# nixie_peripherals.net
KiCad netlist of a schematic drawn in Altium Designer
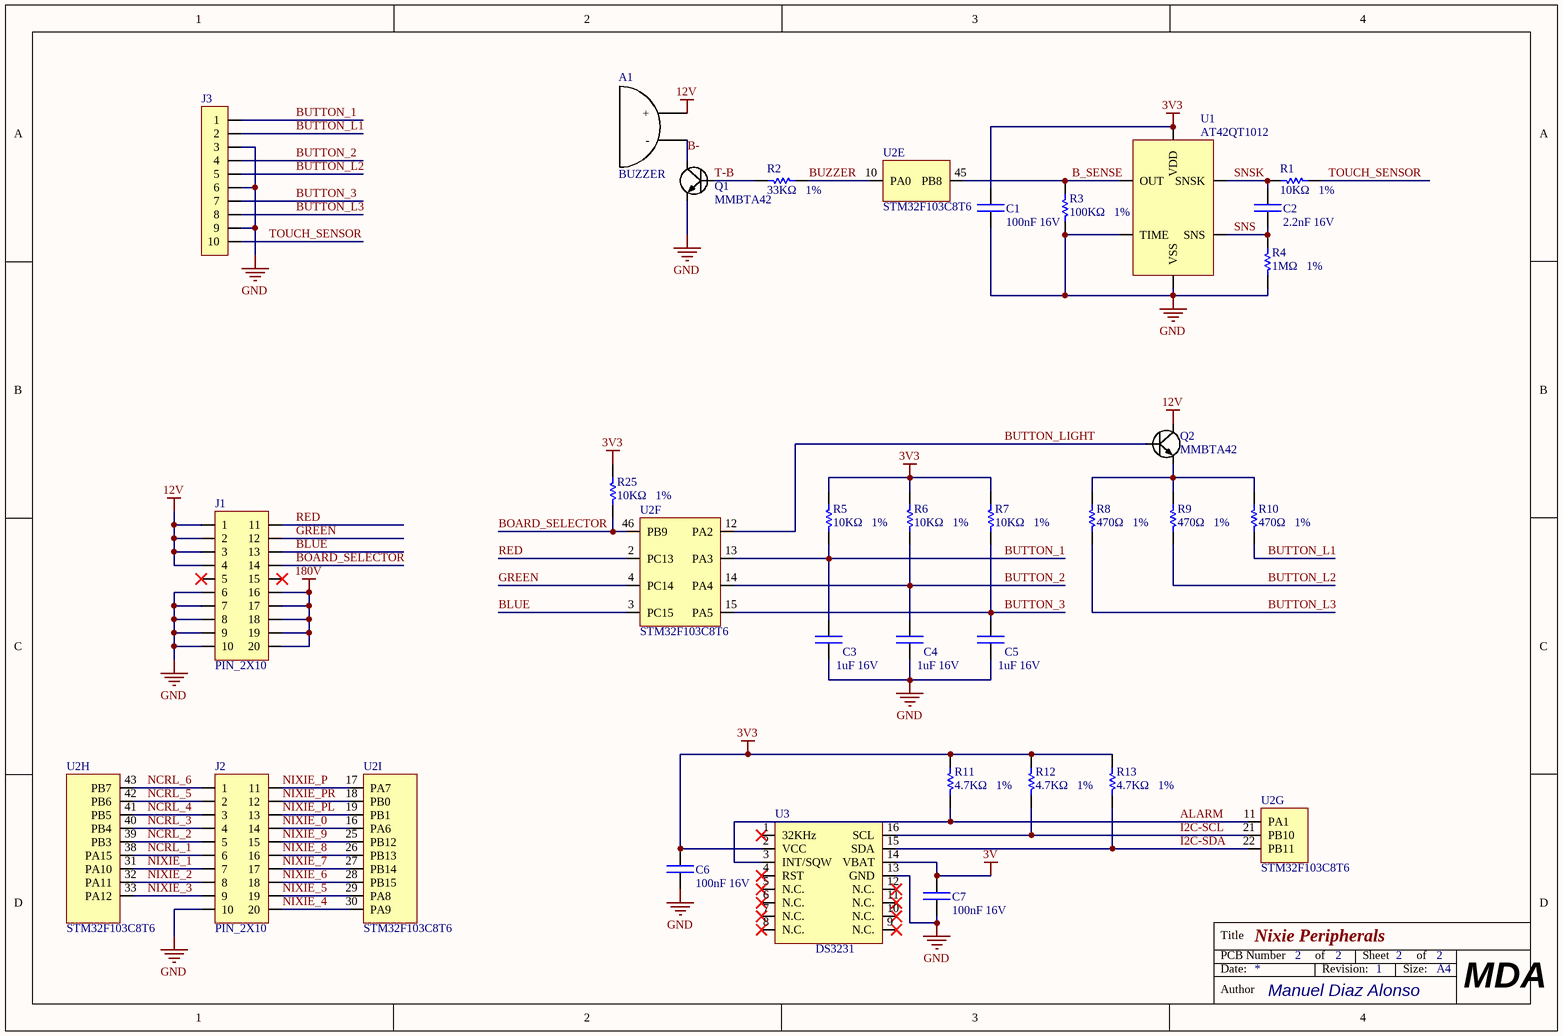
[diagram p0: nixie_peripherals.SchDoc]

(export (version "E")
  (design (tool "Eeschema 10.0.6"))
  (components
    (comp (ref "A1") (value "BUZZER") (footprint "BUZZER") (libsource (lib "Nixielib") (part "BUZZER")))
    (comp (ref "C1") (value "100nF 16V") (footprint "0603") (libsource (lib "Nixielib") (part "CAP")))
    (comp (ref "C2") (value "2.2nF 16V") (footprint "0603") (libsource (lib "Nixielib") (part "CAP")))
    (comp (ref "C3") (value "1uF 16V") (footprint "0603") (libsource (lib "Nixielib") (part "CAP")))
    (comp (ref "C4") (value "1uF 16V") (footprint "0603") (libsource (lib "Nixielib") (part "CAP")))
    (comp (ref "C5") (value "1uF 16V") (footprint "0603") (libsource (lib "Nixielib") (part "CAP")))
    (comp (ref "C6") (value "100nF 16V") (footprint "0603") (libsource (lib "Nixielib") (part "CAP")))
    (comp (ref "C7") (value "100nF 16V") (footprint "0603") (libsource (lib "Nixielib") (part "CAP")))
    (comp (ref "J1")
      (value "PIN_2X10")
      (footprint "PIN_2X10_SKT")
      (description "SSW-110-01-L-D")
      (libsource (lib "MyLib") (part "PIN_2X10"))
    )
    (comp (ref "J2")
      (value "PIN_2X10")
      (footprint "PIN_2X10_SKT")
      (description "SSW-110-01-L-D")
      (libsource (lib "MyLib") (part "PIN_2X10"))
    )
    (comp (ref "J3")
      (value "HEADERx10")
      (footprint "HEADERx10")
      (description "1-282837-0")
      (libsource (lib "Nixielib") (part "HEADERx10"))
    )
    (comp (ref "Q1") (value "MMBTA42") (footprint "SOT-23") (libsource (lib "Nixielib") (part "NPN")))
    (comp (ref "Q2") (value "MMBTA42") (footprint "SOT-23") (libsource (lib "Nixielib") (part "NPN")))
    (comp (ref "R1") (value "10KΩ   1%") (footprint "0603") (libsource (lib "Nixielib") (part "RES")))
    (comp (ref "R2") (value "33KΩ   1%") (footprint "0603") (libsource (lib "Nixielib") (part "RES")))
    (comp (ref "R3") (value "100KΩ   1%") (footprint "0603") (libsource (lib "Nixielib") (part "RES")))
    (comp (ref "R4") (value "1MΩ   1%") (footprint "0603") (libsource (lib "Nixielib") (part "RES")))
    (comp (ref "R5") (value "10KΩ   1%") (footprint "0603") (libsource (lib "Nixielib") (part "RES")))
    (comp (ref "R6") (value "10KΩ   1%") (footprint "0603") (libsource (lib "Nixielib") (part "RES")))
    (comp (ref "R7") (value "10KΩ   1%") (footprint "0603") (libsource (lib "Nixielib") (part "RES")))
    (comp (ref "R8") (value "470Ω   1%") (footprint "0603") (libsource (lib "Nixielib") (part "RES")))
    (comp (ref "R9") (value "470Ω   1%") (footprint "0603") (libsource (lib "Nixielib") (part "RES")))
    (comp (ref "R10") (value "470Ω   1%") (footprint "0603") (libsource (lib "Nixielib") (part "RES")))
    (comp (ref "R11") (value "4.7KΩ   1%") (footprint "0603") (libsource (lib "Nixielib") (part "RES")))
    (comp (ref "R12") (value "4.7KΩ   1%") (footprint "0603") (libsource (lib "Nixielib") (part "RES")))
    (comp (ref "R13") (value "4.7KΩ   1%") (footprint "0603") (libsource (lib "Nixielib") (part "RES")))
    (comp (ref "R25") (value "10KΩ   1%") (footprint "0603") (libsource (lib "Nixielib") (part "RES")))
    (comp (ref "U1")
      (value "AT42QT1012")
      (footprint "SOT-23-6")
      (libsource (lib "Nixielib") (part "AT42QT1012"))
    )
    (comp (ref "U2")
      (value "STM32F103C8T6")
      (footprint "LQFP48")
      (libsource (lib "MyLib") (part "STM32F103C8T6"))
    )
    (comp (ref "U3") (value "DS3231") (footprint "SO16W") (libsource (lib "Nixielib") (part "DS3231")))
  )
  (nets
    (net (code "1") (name "/ALARM") (class "Default")
      (node (ref "R11") (pin "1") (pinfunction "1_1") (pintype "passive"))
      (node (ref "U2") (pin "11") (pinfunction "PA1_11") (pintype "passive"))
      (node (ref "U3") (pin "3") (pinfunction "INT/SQW_3") (pintype "passive"))
    )
    (net (code "2") (name "/B-") (class "Default")
      (node (ref "A1") (pin "2") (pinfunction "-_2") (pintype "passive"))
      (node (ref "Q1") (pin "3") (pinfunction "C_3") (pintype "passive"))
    )
    (net (code "3") (name "/BLUE") (class "Default")
      (node (ref "J1") (pin "13") (pinfunction "13_13") (pintype "passive"))
      (node (ref "U2") (pin "3") (pinfunction "PC15_3") (pintype "passive"))
    )
    (net (code "4") (name "/BOARD_SELECTOR") (class "Default")
      (node (ref "J1") (pin "14") (pinfunction "14_14") (pintype "passive"))
      (node (ref "R25") (pin "2") (pinfunction "2_2") (pintype "passive"))
      (node (ref "U2") (pin "46") (pinfunction "PB9_46") (pintype "passive"))
    )
    (net (code "5") (name "/BUTTON_1") (class "Default")
      (node (ref "C3") (pin "2") (pinfunction "2_2") (pintype "passive"))
      (node (ref "J3") (pin "1") (pinfunction "1_1") (pintype "passive"))
      (node (ref "R5") (pin "1") (pinfunction "1_1") (pintype "passive"))
      (node (ref "U2") (pin "13") (pinfunction "PA3_13") (pintype "passive"))
    )
    (net (code "6") (name "/BUTTON_2") (class "Default")
      (node (ref "C4") (pin "2") (pinfunction "2_2") (pintype "passive"))
      (node (ref "J3") (pin "4") (pinfunction "4_4") (pintype "passive"))
      (node (ref "R6") (pin "1") (pinfunction "1_1") (pintype "passive"))
      (node (ref "U2") (pin "14") (pinfunction "PA4_14") (pintype "passive"))
    )
    (net (code "7") (name "/BUTTON_3") (class "Default")
      (node (ref "C5") (pin "2") (pinfunction "2_2") (pintype "passive"))
      (node (ref "J3") (pin "7") (pinfunction "7_7") (pintype "passive"))
      (node (ref "R7") (pin "1") (pinfunction "1_1") (pintype "passive"))
      (node (ref "U2") (pin "15") (pinfunction "PA5_15") (pintype "passive"))
    )
    (net (code "8") (name "/BUTTON_L1") (class "Default")
      (node (ref "J3") (pin "2") (pinfunction "2_2") (pintype "passive"))
      (node (ref "R10") (pin "2") (pinfunction "2_2") (pintype "passive"))
    )
    (net (code "9") (name "/BUTTON_L2") (class "Default")
      (node (ref "J3") (pin "5") (pinfunction "5_5") (pintype "passive"))
      (node (ref "R9") (pin "2") (pinfunction "2_2") (pintype "passive"))
    )
    (net (code "10") (name "/BUTTON_L3") (class "Default")
      (node (ref "J3") (pin "8") (pinfunction "8_8") (pintype "passive"))
      (node (ref "R8") (pin "2") (pinfunction "2_2") (pintype "passive"))
    )
    (net (code "11") (name "/BUTTON_LIGHT") (class "Default")
      (node (ref "Q2") (pin "1") (pinfunction "B_1") (pintype "passive"))
      (node (ref "U2") (pin "12") (pinfunction "PA2_12") (pintype "passive"))
    )
    (net (code "12") (name "/BUZZER") (class "Default")
      (node (ref "R2") (pin "2") (pinfunction "2_2") (pintype "passive"))
      (node (ref "U2") (pin "10") (pinfunction "PA0_10") (pintype "passive"))
    )
    (net (code "13") (name "/B_SENSE") (class "Default")
      (node (ref "R3") (pin "2") (pinfunction "2_2") (pintype "passive"))
      (node (ref "U1") (pin "1") (pinfunction "OUT_1") (pintype "passive"))
      (node (ref "U2") (pin "45") (pinfunction "PB8_45") (pintype "passive"))
    )
    (net (code "14") (name "/GREEN") (class "Default")
      (node (ref "J1") (pin "12") (pinfunction "12_12") (pintype "passive"))
      (node (ref "U2") (pin "4") (pinfunction "PC14_4") (pintype "passive"))
    )
    (net (code "15") (name "/I2C-SCL") (class "Default")
      (node (ref "R12") (pin "1") (pinfunction "1_1") (pintype "passive"))
      (node (ref "U2") (pin "21") (pinfunction "PB10_21") (pintype "passive"))
      (node (ref "U3") (pin "16") (pinfunction "SCL_16") (pintype "passive"))
    )
    (net (code "16") (name "/I2C-SDA") (class "Default")
      (node (ref "R13") (pin "1") (pinfunction "1_1") (pintype "passive"))
      (node (ref "U2") (pin "22") (pinfunction "PB11_22") (pintype "passive"))
      (node (ref "U3") (pin "15") (pinfunction "SDA_15") (pintype "passive"))
    )
    (net (code "17") (name "/NCRL_1") (class "Default")
      (node (ref "J2") (pin "6") (pinfunction "6_6") (pintype "passive"))
      (node (ref "U2") (pin "38") (pinfunction "PA15_38") (pintype "passive"))
    )
    (net (code "18") (name "/NCRL_2") (class "Default")
      (node (ref "J2") (pin "5") (pinfunction "5_5") (pintype "passive"))
      (node (ref "U2") (pin "39") (pinfunction "PB3_39") (pintype "passive"))
    )
    (net (code "19") (name "/NCRL_3") (class "Default")
      (node (ref "J2") (pin "4") (pinfunction "4_4") (pintype "passive"))
      (node (ref "U2") (pin "40") (pinfunction "PB4_40") (pintype "passive"))
    )
    (net (code "20") (name "/NCRL_4") (class "Default")
      (node (ref "J2") (pin "3") (pinfunction "3_3") (pintype "passive"))
      (node (ref "U2") (pin "41") (pinfunction "PB5_41") (pintype "passive"))
    )
    (net (code "21") (name "/NCRL_5") (class "Default")
      (node (ref "J2") (pin "2") (pinfunction "2_2") (pintype "passive"))
      (node (ref "U2") (pin "42") (pinfunction "PB6_42") (pintype "passive"))
    )
    (net (code "22") (name "/NCRL_6") (class "Default")
      (node (ref "J2") (pin "1") (pinfunction "1_1") (pintype "passive"))
      (node (ref "U2") (pin "43") (pinfunction "PB7_43") (pintype "passive"))
    )
    (net (code "23") (name "/NIXIE_0") (class "Default")
      (node (ref "J2") (pin "14") (pinfunction "14_14") (pintype "passive"))
      (node (ref "U2") (pin "16") (pinfunction "PA6_16") (pintype "passive"))
    )
    (net (code "24") (name "/NIXIE_1") (class "Default")
      (node (ref "J2") (pin "7") (pinfunction "7_7") (pintype "passive"))
      (node (ref "U2") (pin "31") (pinfunction "PA10_31") (pintype "passive"))
    )
    (net (code "25") (name "/NIXIE_2") (class "Default")
      (node (ref "J2") (pin "8") (pinfunction "8_8") (pintype "passive"))
      (node (ref "U2") (pin "32") (pinfunction "PA11_32") (pintype "passive"))
    )
    (net (code "26") (name "/NIXIE_3") (class "Default")
      (node (ref "J2") (pin "9") (pinfunction "9_9") (pintype "passive"))
      (node (ref "U2") (pin "33") (pinfunction "PA12_33") (pintype "passive"))
    )
    (net (code "27") (name "/NIXIE_4") (class "Default")
      (node (ref "J2") (pin "20") (pinfunction "20_20") (pintype "passive"))
      (node (ref "U2") (pin "30") (pinfunction "PA9_30") (pintype "passive"))
    )
    (net (code "28") (name "/NIXIE_5") (class "Default")
      (node (ref "J2") (pin "19") (pinfunction "19_19") (pintype "passive"))
      (node (ref "U2") (pin "29") (pinfunction "PA8_29") (pintype "passive"))
    )
    (net (code "29") (name "/NIXIE_6") (class "Default")
      (node (ref "J2") (pin "18") (pinfunction "18_18") (pintype "passive"))
      (node (ref "U2") (pin "28") (pinfunction "PB15_28") (pintype "passive"))
    )
    (net (code "30") (name "/NIXIE_7") (class "Default")
      (node (ref "J2") (pin "17") (pinfunction "17_17") (pintype "passive"))
      (node (ref "U2") (pin "27") (pinfunction "PB14_27") (pintype "passive"))
    )
    (net (code "31") (name "/NIXIE_8") (class "Default")
      (node (ref "J2") (pin "16") (pinfunction "16_16") (pintype "passive"))
      (node (ref "U2") (pin "26") (pinfunction "PB13_26") (pintype "passive"))
    )
    (net (code "32") (name "/NIXIE_9") (class "Default")
      (node (ref "J2") (pin "15") (pinfunction "15_15") (pintype "passive"))
      (node (ref "U2") (pin "25") (pinfunction "PB12_25") (pintype "passive"))
    )
    (net (code "33") (name "/NIXIE_P") (class "Default")
      (node (ref "J2") (pin "11") (pinfunction "11_11") (pintype "passive"))
      (node (ref "U2") (pin "17") (pinfunction "PA7_17") (pintype "passive"))
    )
    (net (code "34") (name "/NIXIE_PL") (class "Default")
      (node (ref "J2") (pin "13") (pinfunction "13_13") (pintype "passive"))
      (node (ref "U2") (pin "19") (pinfunction "PB1_19") (pintype "passive"))
    )
    (net (code "35") (name "/NIXIE_PR") (class "Default")
      (node (ref "J2") (pin "12") (pinfunction "12_12") (pintype "passive"))
      (node (ref "U2") (pin "18") (pinfunction "PB0_18") (pintype "passive"))
    )
    (net (code "36") (name "/RED") (class "Default")
      (node (ref "J1") (pin "11") (pinfunction "11_11") (pintype "passive"))
      (node (ref "U2") (pin "2") (pinfunction "PC13_2") (pintype "passive"))
    )
    (net (code "37") (name "/SNS") (class "Default")
      (node (ref "C2") (pin "2") (pinfunction "2_2") (pintype "passive"))
      (node (ref "R4") (pin "1") (pinfunction "1_1") (pintype "passive"))
      (node (ref "U1") (pin "4") (pinfunction "SNS_4") (pintype "passive"))
    )
    (net (code "38") (name "/SNSK") (class "Default")
      (node (ref "C2") (pin "1") (pinfunction "1_1") (pintype "passive"))
      (node (ref "R1") (pin "2") (pinfunction "2_2") (pintype "passive"))
      (node (ref "U1") (pin "3") (pinfunction "SNSK_3") (pintype "passive"))
    )
    (net (code "39") (name "/T-B") (class "Default")
      (node (ref "Q1") (pin "1") (pinfunction "B_1") (pintype "passive"))
      (node (ref "R2") (pin "1") (pinfunction "1_1") (pintype "passive"))
    )
    (net (code "40") (name "/TOUCH_SENSOR") (class "Default")
      (node (ref "J3") (pin "10") (pinfunction "10_10") (pintype "passive"))
      (node (ref "R1") (pin "1") (pinfunction "1_1") (pintype "passive"))
    )
    (net (code "41") (name "3V") (class "Default")
      (node (ref "C7") (pin "2") (pinfunction "2_2") (pintype "passive"))
      (node (ref "U3") (pin "14") (pinfunction "VBAT_14") (pintype "passive"))
    )
    (net (code "42") (name "3V3") (class "Default")
      (node (ref "C1") (pin "1") (pinfunction "1_1") (pintype "passive"))
      (node (ref "C6") (pin "2") (pinfunction "2_2") (pintype "passive"))
      (node (ref "R11") (pin "2") (pinfunction "2_2") (pintype "passive"))
      (node (ref "R12") (pin "2") (pinfunction "2_2") (pintype "passive"))
      (node (ref "R13") (pin "2") (pinfunction "2_2") (pintype "passive"))
      (node (ref "R25") (pin "1") (pinfunction "1_1") (pintype "passive"))
      (node (ref "R5") (pin "2") (pinfunction "2_2") (pintype "passive"))
      (node (ref "R6") (pin "2") (pinfunction "2_2") (pintype "passive"))
      (node (ref "R7") (pin "2") (pinfunction "2_2") (pintype "passive"))
      (node (ref "U1") (pin "5") (pinfunction "VDD_5") (pintype "passive"))
      (node (ref "U3") (pin "2") (pinfunction "VCC_2") (pintype "passive"))
    )
    (net (code "43") (name "12V") (class "Default")
      (node (ref "A1") (pin "1") (pinfunction "+_1") (pintype "passive"))
      (node (ref "J1") (pin "1") (pinfunction "1_1") (pintype "passive"))
      (node (ref "J1") (pin "2") (pinfunction "2_2") (pintype "passive"))
      (node (ref "J1") (pin "3") (pinfunction "3_3") (pintype "passive"))
      (node (ref "J1") (pin "4") (pinfunction "4_4") (pintype "passive"))
      (node (ref "Q2") (pin "3") (pinfunction "C_3") (pintype "passive"))
    )
    (net (code "44") (name "180V") (class "Default")
      (node (ref "J1") (pin "16") (pinfunction "16_16") (pintype "passive"))
      (node (ref "J1") (pin "17") (pinfunction "17_17") (pintype "passive"))
      (node (ref "J1") (pin "18") (pinfunction "18_18") (pintype "passive"))
      (node (ref "J1") (pin "19") (pinfunction "19_19") (pintype "passive"))
      (node (ref "J1") (pin "20") (pinfunction "20_20") (pintype "passive"))
    )
    (net (code "45") (name "GND") (class "Default")
      (node (ref "C1") (pin "2") (pinfunction "2_2") (pintype "passive"))
      (node (ref "C3") (pin "1") (pinfunction "1_1") (pintype "passive"))
      (node (ref "C4") (pin "1") (pinfunction "1_1") (pintype "passive"))
      (node (ref "C5") (pin "1") (pinfunction "1_1") (pintype "passive"))
      (node (ref "C6") (pin "1") (pinfunction "1_1") (pintype "passive"))
      (node (ref "C7") (pin "1") (pinfunction "1_1") (pintype "passive"))
      (node (ref "J1") (pin "10") (pinfunction "10_10") (pintype "passive"))
      (node (ref "J1") (pin "6") (pinfunction "6_6") (pintype "passive"))
      (node (ref "J1") (pin "7") (pinfunction "7_7") (pintype "passive"))
      (node (ref "J1") (pin "8") (pinfunction "8_8") (pintype "passive"))
      (node (ref "J1") (pin "9") (pinfunction "9_9") (pintype "passive"))
      (node (ref "J2") (pin "10") (pinfunction "10_10") (pintype "passive"))
      (node (ref "J3") (pin "3") (pinfunction "3_3") (pintype "passive"))
      (node (ref "J3") (pin "6") (pinfunction "6_6") (pintype "passive"))
      (node (ref "J3") (pin "9") (pinfunction "9_9") (pintype "passive"))
      (node (ref "Q1") (pin "2") (pinfunction "E_2") (pintype "passive"))
      (node (ref "R3") (pin "1") (pinfunction "1_1") (pintype "passive"))
      (node (ref "R4") (pin "2") (pinfunction "2_2") (pintype "passive"))
      (node (ref "U1") (pin "2") (pinfunction "VSS_2") (pintype "passive"))
      (node (ref "U1") (pin "6") (pinfunction "TIME_6") (pintype "passive"))
      (node (ref "U3") (pin "13") (pinfunction "GND_13") (pintype "passive"))
    )
    (net (code "46") (name "Net-(Q2-E)") (class "Default")
      (node (ref "Q2") (pin "2") (pinfunction "E_2") (pintype "passive"))
      (node (ref "R10") (pin "1") (pinfunction "1_1") (pintype "passive"))
      (node (ref "R8") (pin "1") (pinfunction "1_1") (pintype "passive"))
      (node (ref "R9") (pin "1") (pinfunction "1_1") (pintype "passive"))
    )
    (net (code "47") (name "unconnected-(J1-Pad5)") (class "Default")
      (node (ref "J1") (pin "5") (pinfunction "5_5") (pintype "passive+no_connect"))
    )
    (net (code "48") (name "unconnected-(J1-Pad15)") (class "Default")
      (node (ref "J1") (pin "15") (pinfunction "15_15") (pintype "passive+no_connect"))
    )
    (net (code "49") (name "unconnected-(U3-32KHz-Pad1)") (class "Default")
      (node (ref "U3") (pin "1") (pinfunction "32KHz_1") (pintype "passive+no_connect"))
    )
    (net (code "50") (name "unconnected-(U3-N.C.-Pad5)") (class "Default")
      (node (ref "U3") (pin "5") (pinfunction "N.C._5") (pintype "passive+no_connect"))
    )
    (net (code "51") (name "unconnected-(U3-N.C.-Pad6)") (class "Default")
      (node (ref "U3") (pin "6") (pinfunction "N.C._6") (pintype "passive+no_connect"))
    )
    (net (code "52") (name "unconnected-(U3-N.C.-Pad7)") (class "Default")
      (node (ref "U3") (pin "7") (pinfunction "N.C._7") (pintype "passive+no_connect"))
    )
    (net (code "53") (name "unconnected-(U3-N.C.-Pad8)") (class "Default")
      (node (ref "U3") (pin "8") (pinfunction "N.C._8") (pintype "passive+no_connect"))
    )
    (net (code "54") (name "unconnected-(U3-N.C.-Pad9)") (class "Default")
      (node (ref "U3") (pin "9") (pinfunction "N.C._9") (pintype "passive+no_connect"))
    )
    (net (code "55") (name "unconnected-(U3-N.C.-Pad10)") (class "Default")
      (node (ref "U3") (pin "10") (pinfunction "N.C._10") (pintype "passive+no_connect"))
    )
    (net (code "56") (name "unconnected-(U3-N.C.-Pad11)") (class "Default")
      (node (ref "U3") (pin "11") (pinfunction "N.C._11") (pintype "passive+no_connect"))
    )
    (net (code "57") (name "unconnected-(U3-N.C.-Pad12)") (class "Default")
      (node (ref "U3") (pin "12") (pinfunction "N.C._12") (pintype "passive+no_connect"))
    )
    (net (code "58") (name "unconnected-(U3-RST-Pad4)") (class "Default")
      (node (ref "U3") (pin "4") (pinfunction "RST_4") (pintype "passive+no_connect"))
    )
  )
)
